# MCU.net
KiCad netlist of a schematic drawn in Altium Designer
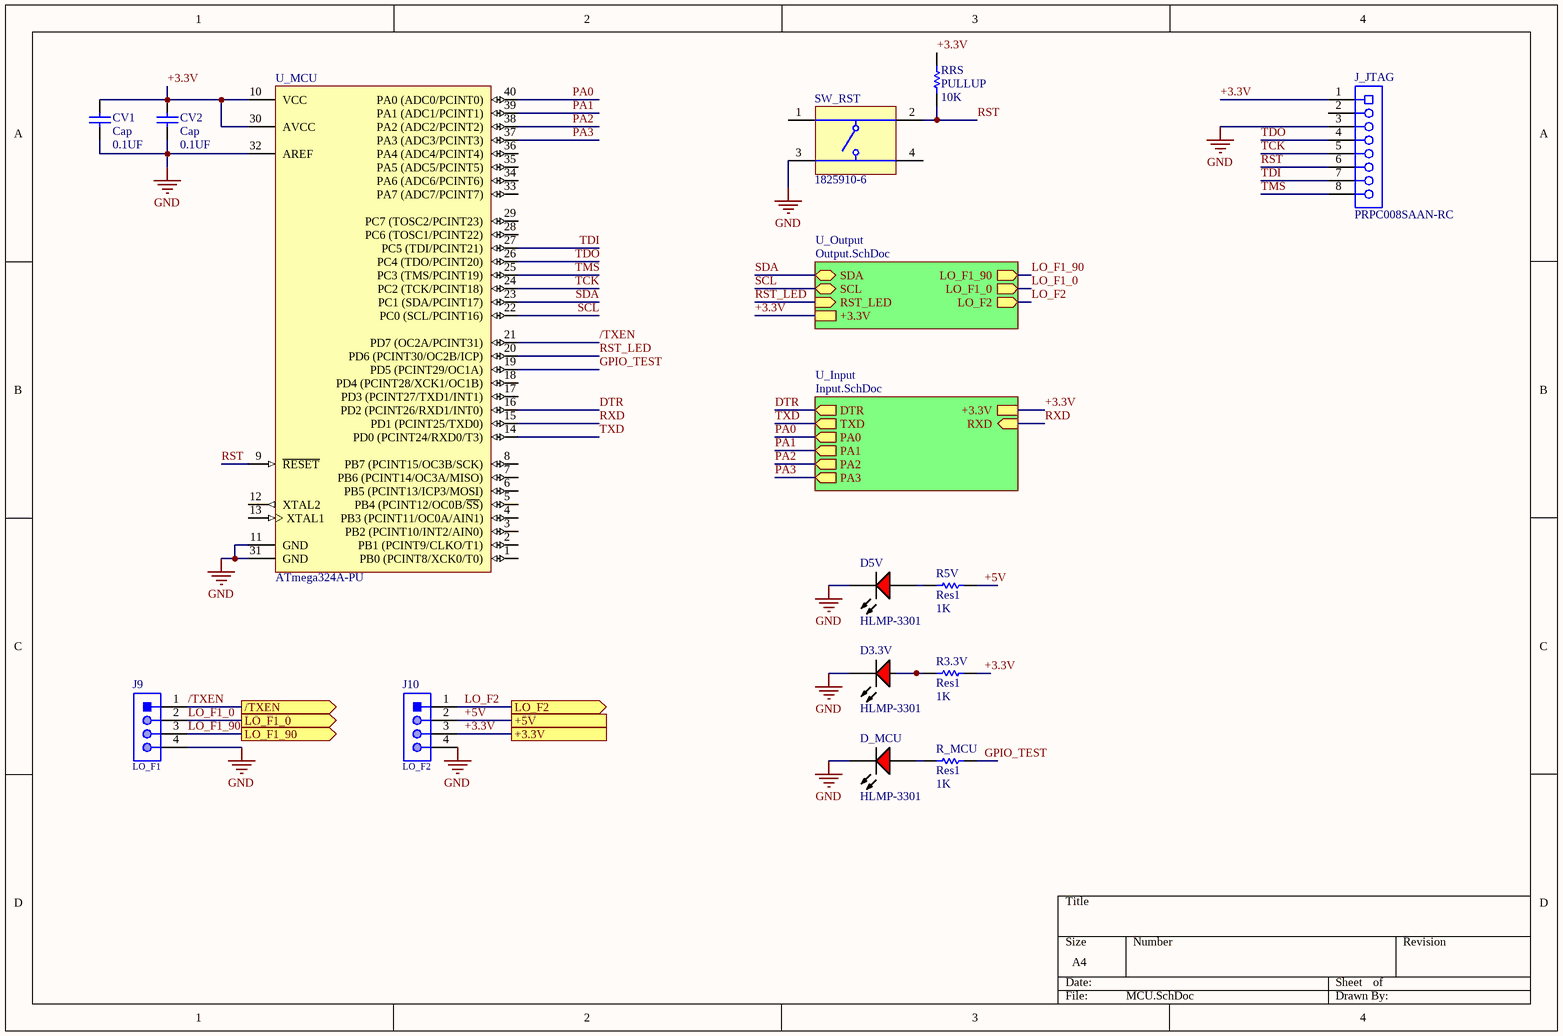
[diagram p0: MCU.SchDoc]

(export (version "E")
  (design (tool "Eeschema 10.0.6"))
  (components
    (comp (ref "CV1")
      (value "Cap")
      (footprint "RADIAL-0.1")
      (description "Capacitor")
      (fields
        (field (name "ALTIUM_VALUE") "0.1UF")
        (field (name "MANUFACTURER PART NUMBER") "K104M15X7RF5TH5")
        (field (name "PUBLISHER") "Altium Limited")
      )
      (libsource (lib "ECE295-Capacitors-TH") (part "CAP CER 0.1UF 50V X7R RADIAL"))
    )
    (comp (ref "CV2")
      (value "Cap")
      (footprint "RADIAL-0.1")
      (description "Capacitor")
      (fields
        (field (name "ALTIUM_VALUE") "0.1UF")
        (field (name "MANUFACTURER PART NUMBER") "K104M15X7RF5TH5")
        (field (name "PUBLISHER") "Altium Limited")
      )
      (libsource (lib "ECE295-Capacitors-TH") (part "CAP CER 0.1UF 50V X7R RADIAL"))
    )
    (comp (ref "D3.3V")
      (value "HLMP-3301")
      (footprint "AVAG-HLMP-3301-2")
      (description "T-1 3/4 (5 mm) Diffused LED Lamp, 1.9 V, -40 to 100 degC, 2-Pin THD, RoHS, Bulk")
      (fields (field (name "MANUFACTURER") "Avago"))
      (libsource (lib "Altium Content Vault") (part "LED-RED-K1A2-2"))
    )
    (comp (ref "D5V")
      (value "HLMP-3301")
      (footprint "AVAG-HLMP-3301-2")
      (description "T-1 3/4 (5 mm) Diffused LED Lamp, 1.9 V, -40 to 100 degC, 2-Pin THD, RoHS, Bulk")
      (fields (field (name "MANUFACTURER") "Avago"))
      (libsource (lib "Altium Content Vault") (part "LED-RED-K1A2-2"))
    )
    (comp (ref "D_MCU")
      (value "HLMP-3301")
      (footprint "AVAG-HLMP-3301-2")
      (description "T-1 3/4 (5 mm) Diffused LED Lamp, 1.9 V, -40 to 100 degC, 2-Pin THD, RoHS, Bulk")
      (fields (field (name "MANUFACTURER") "Avago"))
      (libsource (lib "Altium Content Vault") (part "LED-RED-K1A2-2"))
    )
    (comp (ref "J9")
      (value "LO_F1")
      (footprint "61300411121")
      (description "THT Vertical Pin Header WR-PHD, Pitch 2.54 mm, Single Row, 4 pins")
      (fields
        (field (name "MANUFACTURER") "Wurth Elektronik")
        (field (name "PART NUMBER") "61300411121")
        (field (name "PUBLISHER") "WurthElektronik")
      )
      (libsource (lib "Altium Content Vault") (part "WE-CN-1P-M-R4"))
    )
    (comp (ref "J10")
      (value "LO_F2")
      (footprint "61300411121")
      (description "THT Vertical Pin Header WR-PHD, Pitch 2.54 mm, Single Row, 4 pins")
      (fields
        (field (name "MANUFACTURER") "Wurth Elektronik")
        (field (name "PART NUMBER") "61300411121")
        (field (name "PUBLISHER") "WurthElektronik")
      )
      (libsource (lib "Altium Content Vault") (part "WE-CN-1P-M-R4"))
    )
    (comp (ref "J_JTAG")
      (value "PRPC008SAAN-RC")
      (footprint "SLIN-PPPC081LFBN-RC_V")
      (libsource (lib "Altium Content Vault") (part "CN-1P-F-R8"))
    )
    (comp (ref "R3.3V")
      (value "Res1")
      (footprint "AXIAL-0.1-RES")
      (description "Resistor")
      (fields
        (field (name "MANUFACTURER PART NUMBER") "CFR-25JB-52-1K")
        (field (name "TOLERANCE") "0.05")
        (field (name "ALTIUM_VALUE") "1K")
        (field (name "PUBLISHER") "Altium Limited")
      )
      (libsource (lib "ECE295-Resistors-TH") (part "RES 1K OHM 5% 1/4W AXIAL"))
    )
    (comp (ref "R5V")
      (value "Res1")
      (footprint "AXIAL-0.1-RES")
      (description "Resistor")
      (fields
        (field (name "MANUFACTURER PART NUMBER") "CFR-25JB-52-1K")
        (field (name "TOLERANCE") "0.05")
        (field (name "ALTIUM_VALUE") "1K")
        (field (name "PUBLISHER") "Altium Limited")
      )
      (libsource (lib "ECE295-Resistors-TH") (part "RES 1K OHM 5% 1/4W AXIAL"))
    )
    (comp (ref "RRS")
      (value "PULLUP")
      (footprint "AXIAL-0.1-RES")
      (description "Resistor")
      (fields
        (field (name "ALTIUM_VALUE") "10K")
        (field (name "MANUFACTURER PART NUMBER") "CFR-25JB-52-10K")
        (field (name "TOLERANCE") "0.05")
        (field (name "PUBLISHER") "Altium Limited")
      )
      (libsource (lib "ECE295-Resistors-TH") (part "RES 10K OHM 5% 1/4W AXIAL"))
    )
    (comp (ref "R_MCU")
      (value "Res1")
      (footprint "AXIAL-0.1-RES")
      (description "Resistor")
      (fields
        (field (name "MANUFACTURER PART NUMBER") "CFR-25JB-52-1K")
        (field (name "TOLERANCE") "0.05")
        (field (name "ALTIUM_VALUE") "1K")
        (field (name "PUBLISHER") "Altium Limited")
      )
      (libsource (lib "ECE295-Resistors-TH") (part "RES 1K OHM 5% 1/4W AXIAL"))
    )
    (comp (ref "SW_RST")
      (value "1825910-6")
      (footprint "TECO-1825910-6_V")
      (description "Tact Switch, SPST-NO, 0.05 A, -35 to 85 degC, 4-Pin THD, RoHS, Bulk")
      (fields (field (name "MANUFACTURER") "TE Connectivity"))
      (libsource (lib "Altium Content Vault") (part "SW-SPST-4_A"))
    )
    (comp (ref "U_MCU")
      (value "ATmega324A-PU")
      (footprint "40P6")
      (libsource (lib "Altium Content Vault") (part "MC-8B-ATM128-IL40"))
    )
  )
  (nets
    (net (code "1") (name "/+3.3V") (class "Default")
      (node (ref "CV1") (pin "2") (pinfunction "2_2") (pintype "passive"))
      (node (ref "CV2") (pin "2") (pinfunction "2_2") (pintype "passive"))
      (node (ref "J10") (pin "3") (pinfunction "3_3") (pintype "passive"))
      (node (ref "J_JTAG") (pin "1") (pinfunction "1_1") (pintype "passive"))
      (node (ref "R3.3V") (pin "2") (pinfunction "2_2") (pintype "passive"))
      (node (ref "RRS") (pin "2") (pinfunction "2_2") (pintype "passive"))
      (node (ref "U_MCU") (pin "10") (pinfunction "VCC_10") (pintype "power_in"))
      (node (ref "U_MCU") (pin "30") (pinfunction "AVCC_30") (pintype "power_in"))
    )
    (net (code "2") (name "/+5V") (class "Default")
      (node (ref "J10") (pin "2") (pinfunction "2_2") (pintype "passive"))
      (node (ref "R5V") (pin "2") (pinfunction "2_2") (pintype "passive"))
    )
    (net (code "3") (name "/DTR") (class "Default")
      (node (ref "U_MCU") (pin "16") (pinfunction "PD2_(PCINT26/RXD1/INT0)_16") (pintype "bidirectional"))
    )
    (net (code "4") (name "/GPIO_TEST") (class "Default")
      (node (ref "R_MCU") (pin "2") (pinfunction "2_2") (pintype "passive"))
      (node (ref "U_MCU") (pin "19") (pinfunction "PD5_(PCINT29/OC1A)_19") (pintype "bidirectional"))
    )
    (net (code "5") (name "/LO_F1_0") (class "Default")
      (node (ref "J9") (pin "2") (pinfunction "2_2") (pintype "passive"))
    )
    (net (code "6") (name "/LO_F1_90") (class "Default")
      (node (ref "J9") (pin "3") (pinfunction "3_3") (pintype "passive"))
    )
    (net (code "7") (name "/LO_F2") (class "Default")
      (node (ref "J10") (pin "1") (pinfunction "1_1") (pintype "passive"))
    )
    (net (code "8") (name "/PA0") (class "Default")
      (node (ref "U_MCU") (pin "40") (pinfunction "PA0_(ADC0/PCINT0)_40") (pintype "bidirectional"))
    )
    (net (code "9") (name "/PA1") (class "Default")
      (node (ref "U_MCU") (pin "39") (pinfunction "PA1_(ADC1/PCINT1)_39") (pintype "bidirectional"))
    )
    (net (code "10") (name "/PA2") (class "Default")
      (node (ref "U_MCU") (pin "38") (pinfunction "PA2_(ADC2/PCINT2)_38") (pintype "bidirectional"))
    )
    (net (code "11") (name "/PA3") (class "Default")
      (node (ref "U_MCU") (pin "37") (pinfunction "PA3_(ADC3/PCINT3)_37") (pintype "bidirectional"))
    )
    (net (code "12") (name "/RST") (class "Default")
      (node (ref "J_JTAG") (pin "6") (pinfunction "6_6") (pintype "passive"))
      (node (ref "RRS") (pin "1") (pinfunction "1_1") (pintype "passive"))
      (node (ref "SW_RST") (pin "2") (pinfunction "2_2") (pintype "passive"))
      (node (ref "U_MCU") (pin "9") (pinfunction "~{RESET}_9") (pintype "input"))
    )
    (net (code "13") (name "/RST_LED") (class "Default")
      (node (ref "U_MCU") (pin "20") (pinfunction "PD6_(PCINT30/OC2B/ICP)_20") (pintype "bidirectional"))
    )
    (net (code "14") (name "/RXD") (class "Default")
      (node (ref "U_MCU") (pin "15") (pinfunction "PD1_(PCINT25/TXD0)_15") (pintype "bidirectional"))
    )
    (net (code "15") (name "/SCL") (class "Default")
      (node (ref "U_MCU") (pin "22") (pinfunction "PC0_(SCL/PCINT16)_22") (pintype "bidirectional"))
    )
    (net (code "16") (name "/SDA") (class "Default")
      (node (ref "U_MCU") (pin "23") (pinfunction "PC1_(SDA/PCINT17)_23") (pintype "bidirectional"))
    )
    (net (code "17") (name "/TCK") (class "Default")
      (node (ref "J_JTAG") (pin "5") (pinfunction "5_5") (pintype "passive"))
      (node (ref "U_MCU") (pin "24") (pinfunction "PC2_(TCK/PCINT18)_24") (pintype "bidirectional"))
    )
    (net (code "18") (name "/TDI") (class "Default")
      (node (ref "J_JTAG") (pin "7") (pinfunction "7_7") (pintype "passive"))
      (node (ref "U_MCU") (pin "27") (pinfunction "PC5_(TDI/PCINT21)_27") (pintype "bidirectional"))
    )
    (net (code "19") (name "/TDO") (class "Default")
      (node (ref "J_JTAG") (pin "4") (pinfunction "4_4") (pintype "passive"))
      (node (ref "U_MCU") (pin "26") (pinfunction "PC4_(TDO/PCINT20)_26") (pintype "bidirectional"))
    )
    (net (code "20") (name "/TMS") (class "Default")
      (node (ref "J_JTAG") (pin "8") (pinfunction "8_8") (pintype "passive"))
      (node (ref "U_MCU") (pin "25") (pinfunction "PC3_(TMS/PCINT19)_25") (pintype "bidirectional"))
    )
    (net (code "21") (name "/TXD") (class "Default")
      (node (ref "U_MCU") (pin "14") (pinfunction "PD0_(PCINT24/RXD0/T3)_14") (pintype "bidirectional"))
    )
    (net (code "22") (name "/{slash}TXEN") (class "Default")
      (node (ref "J9") (pin "1") (pinfunction "1_1") (pintype "passive"))
      (node (ref "U_MCU") (pin "21") (pinfunction "PD7_(OC2A/PCINT31)_21") (pintype "bidirectional"))
    )
    (net (code "23") (name "GND") (class "Default")
      (node (ref "CV1") (pin "1") (pinfunction "1_1") (pintype "passive"))
      (node (ref "CV2") (pin "1") (pinfunction "1_1") (pintype "passive"))
      (node (ref "D3.3V") (pin "1") (pinfunction "K_1") (pintype "passive"))
      (node (ref "D5V") (pin "1") (pinfunction "K_1") (pintype "passive"))
      (node (ref "D_MCU") (pin "1") (pinfunction "K_1") (pintype "passive"))
      (node (ref "J10") (pin "4") (pinfunction "4_4") (pintype "passive"))
      (node (ref "J9") (pin "4") (pinfunction "4_4") (pintype "passive"))
      (node (ref "J_JTAG") (pin "3") (pinfunction "3_3") (pintype "passive"))
      (node (ref "SW_RST") (pin "3") (pinfunction "3_3") (pintype "passive"))
      (node (ref "U_MCU") (pin "11") (pinfunction "GND_11") (pintype "power_in"))
      (node (ref "U_MCU") (pin "31") (pinfunction "GND_31") (pintype "power_in"))
      (node (ref "U_MCU") (pin "32") (pinfunction "AREF_32") (pintype "power_in"))
    )
    (net (code "24") (name "Net-(D3.3V-A)") (class "Default")
      (node (ref "D3.3V") (pin "2") (pinfunction "A_2") (pintype "passive"))
      (node (ref "R3.3V") (pin "1") (pinfunction "1_1") (pintype "passive"))
    )
    (net (code "25") (name "Net-(D5V-A)") (class "Default")
      (node (ref "D5V") (pin "2") (pinfunction "A_2") (pintype "passive"))
      (node (ref "R5V") (pin "1") (pinfunction "1_1") (pintype "passive"))
    )
    (net (code "26") (name "Net-(D_MCU-A)") (class "Default")
      (node (ref "D_MCU") (pin "2") (pinfunction "A_2") (pintype "passive"))
      (node (ref "R_MCU") (pin "1") (pinfunction "1_1") (pintype "passive"))
    )
    (net (code "27") (name "unconnected-(J_JTAG-Pad2)") (class "Default")
      (node (ref "J_JTAG") (pin "2") (pinfunction "2_2") (pintype "passive"))
    )
    (net (code "28") (name "unconnected-(SW_RST-Pad1)") (class "Default")
      (node (ref "SW_RST") (pin "1") (pinfunction "1_1") (pintype "passive"))
    )
    (net (code "29") (name "unconnected-(SW_RST-Pad4)") (class "Default")
      (node (ref "SW_RST") (pin "4") (pinfunction "4_4") (pintype "passive"))
    )
    (net (code "30") (name "unconnected-(U_MCU-PA4_(ADC4{slash}PCINT4)-Pad36)") (class "Default")
      (node (ref "U_MCU") (pin "36") (pinfunction "PA4_(ADC4/PCINT4)_36") (pintype "bidirectional"))
    )
    (net (code "31") (name "unconnected-(U_MCU-PA5_(ADC5{slash}PCINT5)-Pad35)") (class "Default")
      (node (ref "U_MCU") (pin "35") (pinfunction "PA5_(ADC5/PCINT5)_35") (pintype "bidirectional"))
    )
    (net (code "32") (name "unconnected-(U_MCU-PA6_(ADC6{slash}PCINT6)-Pad34)") (class "Default")
      (node (ref "U_MCU") (pin "34") (pinfunction "PA6_(ADC6/PCINT6)_34") (pintype "bidirectional"))
    )
    (net (code "33") (name "unconnected-(U_MCU-PA7_(ADC7{slash}PCINT7)-Pad33)") (class "Default")
      (node (ref "U_MCU") (pin "33") (pinfunction "PA7_(ADC7/PCINT7)_33") (pintype "bidirectional"))
    )
    (net (code "34") (name "unconnected-(U_MCU-PB0_(PCINT8{slash}XCK0{slash}T0)-Pad1)") (class "Default")
      (node (ref "U_MCU") (pin "1") (pinfunction "PB0_(PCINT8/XCK0/T0)_1") (pintype "bidirectional"))
    )
    (net (code "35") (name "unconnected-(U_MCU-PB1_(PCINT9{slash}CLKO{slash}T1)-Pad2)") (class "Default")
      (node (ref "U_MCU") (pin "2") (pinfunction "PB1_(PCINT9/CLKO/T1)_2") (pintype "bidirectional"))
    )
    (net (code "36") (name "unconnected-(U_MCU-PB2_(PCINT10{slash}INT2{slash}AIN0)-Pad3)") (class "Default")
      (node (ref "U_MCU") (pin "3") (pinfunction "PB2_(PCINT10/INT2/AIN0)_3") (pintype "bidirectional"))
    )
    (net (code "37") (name "unconnected-(U_MCU-PB3_(PCINT11{slash}OC0A{slash}AIN1)-Pad4)") (class "Default")
      (node (ref "U_MCU") (pin "4") (pinfunction "PB3_(PCINT11/OC0A/AIN1)_4") (pintype "bidirectional"))
    )
    (net (code "38") (name "unconnected-(U_MCU-PB4_(PCINT12{slash}OC0B{slash}~{SS})-Pad5)") (class "Default")
      (node (ref "U_MCU") (pin "5") (pinfunction "PB4_(PCINT12/OC0B/~{SS})_5") (pintype "bidirectional"))
    )
    (net (code "39") (name "unconnected-(U_MCU-PB5_(PCINT13{slash}ICP3{slash}MOSI)-Pad6)") (class "Default")
      (node (ref "U_MCU") (pin "6") (pinfunction "PB5_(PCINT13/ICP3/MOSI)_6") (pintype "bidirectional"))
    )
    (net (code "40") (name "unconnected-(U_MCU-PB6_(PCINT14{slash}OC3A{slash}MISO)-Pad7)") (class "Default")
      (node (ref "U_MCU") (pin "7") (pinfunction "PB6_(PCINT14/OC3A/MISO)_7") (pintype "bidirectional"))
    )
    (net (code "41") (name "unconnected-(U_MCU-PB7_(PCINT15{slash}OC3B{slash}SCK)-Pad8)") (class "Default")
      (node (ref "U_MCU") (pin "8") (pinfunction "PB7_(PCINT15/OC3B/SCK)_8") (pintype "bidirectional"))
    )
    (net (code "42") (name "unconnected-(U_MCU-PC6_(TOSC1{slash}PCINT22)-Pad28)") (class "Default")
      (node (ref "U_MCU") (pin "28") (pinfunction "PC6_(TOSC1/PCINT22)_28") (pintype "bidirectional"))
    )
    (net (code "43") (name "unconnected-(U_MCU-PC7_(TOSC2{slash}PCINT23)-Pad29)") (class "Default")
      (node (ref "U_MCU") (pin "29") (pinfunction "PC7_(TOSC2/PCINT23)_29") (pintype "bidirectional"))
    )
    (net (code "44") (name "unconnected-(U_MCU-PD3_(PCINT27{slash}TXD1{slash}INT1)-Pad17)") (class "Default")
      (node (ref "U_MCU") (pin "17") (pinfunction "PD3_(PCINT27/TXD1/INT1)_17") (pintype "bidirectional"))
    )
    (net (code "45") (name "unconnected-(U_MCU-PD4_(PCINT28{slash}XCK1{slash}OC1B)-Pad18)") (class "Default")
      (node (ref "U_MCU") (pin "18") (pinfunction "PD4_(PCINT28/XCK1/OC1B)_18") (pintype "bidirectional"))
    )
    (net (code "46") (name "unconnected-(U_MCU-XTAL1-Pad13)") (class "Default")
      (node (ref "U_MCU") (pin "13") (pinfunction "XTAL1_13") (pintype "input"))
    )
    (net (code "47") (name "unconnected-(U_MCU-XTAL2-Pad12)") (class "Default")
      (node (ref "U_MCU") (pin "12") (pinfunction "XTAL2_12") (pintype "output"))
    )
  )
)
